# Sensor.net
KiCad netlist of a schematic drawn in Altium Designer
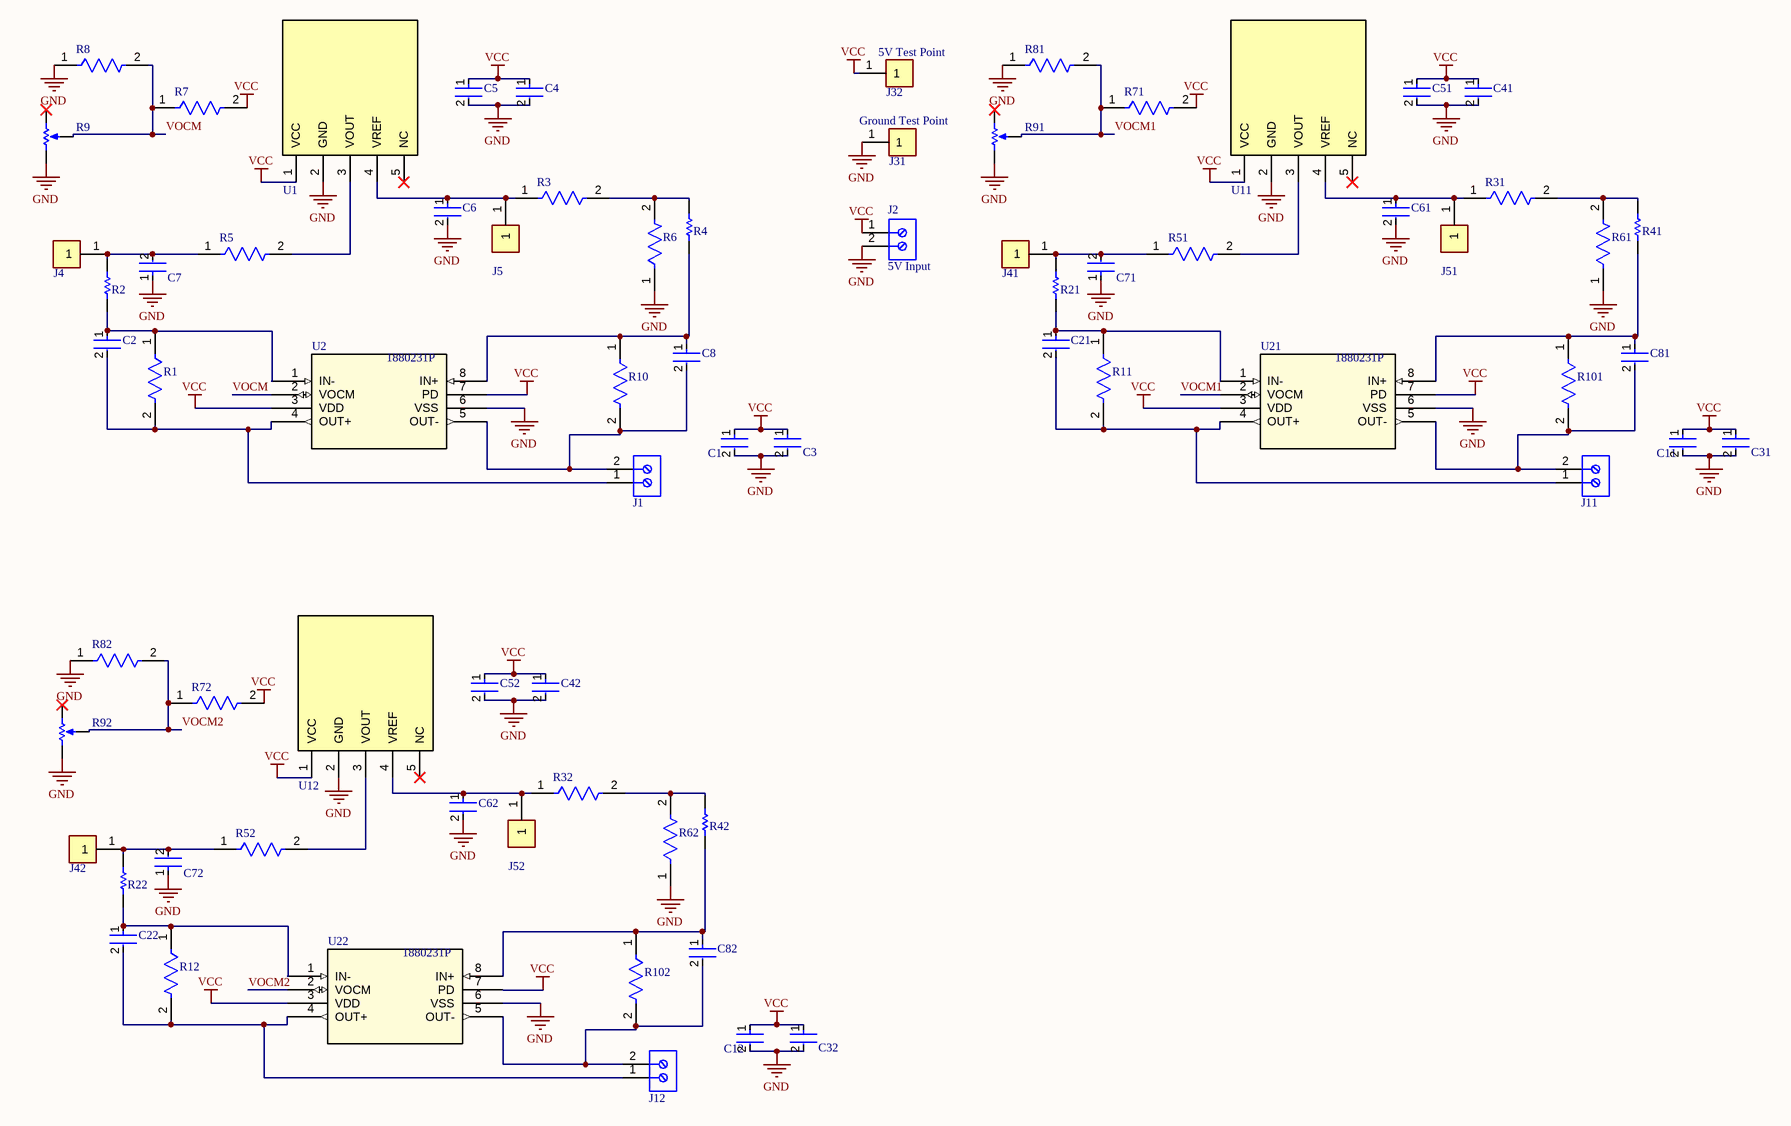
[diagram p0: Sensor.SchDoc]

(export (version "E")
  (design (tool "Eeschema 10.0.6"))
  (components
    (comp (ref "C1")
      (value "0805YC105KAT2A")
      (footprint "FP-0805-L_2_01_0_2-W_1_25-IPC_A")
      (description "General Purpose Ceramic Capacitor, 0805, 1uF, 10%, X7R, 15%, 16V")
      (fields (field (name "TOLERANCE") "10%") (field (name "VOLTAGE") "16V"))
      (libsource (lib "Altium Content Vault") (part "b4654b650e69147ec39a6b967a45e02"))
    )
    (comp (ref "C2")
      (value "06035A100JAT2A")
      (footprint "FP-0603-L_1_6_0_15-W_0_81-MFG")
      (description "General Purpose Ceramic Capacitor, 0603, 10pF, 5%, NP0, 30ppm/°C, 50V")
      (fields (field (name "TOLERANCE") "5%") (field (name "VOLTAGE") "50V"))
      (libsource (lib "Altium Content Vault") (part "02cd4be3c70576c341d710602a673aa"))
    )
    (comp (ref "C3")
      (value "CL21B104KACNNNC")
      (footprint "FP-CL21-IPC_C")
      (description "CL21 Series 0805 100nF 25V ±10% Tolerance X7R Multilayer Ceramic Chip Capacitor")
      (fields (field (name "VOLTAGE") "25V") (field (name "TOLERANCE") "10%"))
      (libsource (lib "Altium Content Vault") (part "b4654b650e69147ec39a6b967a45e02"))
    )
    (comp (ref "C4")
      (value "CL21A106KPFNNNG")
      (footprint "FP-CL21-IPC_B")
      (description "CL21 Series 0805 10uF 10V ±10% Tolerance X5R Multilayer Ceramic Chip Capacitor")
      (fields (field (name "VOLTAGE") "10V") (field (name "TOLERANCE") "10%"))
      (libsource (lib "Altium Content Vault") (part "b4654b650e69147ec39a6b967a45e02"))
    )
    (comp (ref "C5")
      (value "CL21B104KACNNNC")
      (footprint "FP-CL21-IPC_C")
      (description "CL21 Series 0805 100nF 25V ±10% Tolerance X7R Multilayer Ceramic Chip Capacitor")
      (fields (field (name "VOLTAGE") "25V") (field (name "TOLERANCE") "10%"))
      (libsource (lib "Altium Content Vault") (part "b4654b650e69147ec39a6b967a45e02"))
    )
    (comp (ref "C6")
      (value "CL21B104KACNNNC")
      (footprint "FP-CL21-IPC_C")
      (description "CL21 Series 0805 100nF 25V ±10% Tolerance X7R Multilayer Ceramic Chip Capacitor")
      (fields (field (name "VOLTAGE") "25V") (field (name "TOLERANCE") "10%"))
      (libsource (lib "Altium Content Vault") (part "b4654b650e69147ec39a6b967a45e02"))
    )
    (comp (ref "C7")
      (value "06035A100JAT2A")
      (footprint "FP-0603-L_1_6_0_15-W_0_81-MFG")
      (description "General Purpose Ceramic Capacitor, 0603, 10pF, 5%, NP0, 30ppm/°C, 50V")
      (fields (field (name "TOLERANCE") "5%") (field (name "VOLTAGE") "50V"))
      (libsource (lib "Altium Content Vault") (part "02cd4be3c70576c341d710602a673aa"))
    )
    (comp (ref "C8")
      (value "06035A100JAT2A")
      (footprint "FP-0603-L_1_6_0_15-W_0_81-MFG")
      (description "General Purpose Ceramic Capacitor, 0603, 10pF, 5%, NP0, 30ppm/°C, 50V")
      (fields (field (name "TOLERANCE") "5%") (field (name "VOLTAGE") "50V"))
      (libsource (lib "Altium Content Vault") (part "02cd4be3c70576c341d710602a673aa"))
    )
    (comp (ref "C11")
      (value "0805YC105KAT2A")
      (footprint "FP-0805-L_2_01_0_2-W_1_25-IPC_A")
      (description "General Purpose Ceramic Capacitor, 0805, 1uF, 10%, X7R, 15%, 16V")
      (fields (field (name "TOLERANCE") "10%") (field (name "VOLTAGE") "16V"))
      (libsource (lib "Altium Content Vault") (part "b4654b650e69147ec39a6b967a45e02"))
    )
    (comp (ref "C12")
      (value "0805YC105KAT2A")
      (footprint "FP-0805-L_2_01_0_2-W_1_25-IPC_A")
      (description "General Purpose Ceramic Capacitor, 0805, 1uF, 10%, X7R, 15%, 16V")
      (fields (field (name "TOLERANCE") "10%") (field (name "VOLTAGE") "16V"))
      (libsource (lib "Altium Content Vault") (part "b4654b650e69147ec39a6b967a45e02"))
    )
    (comp (ref "C21")
      (value "06035A100JAT2A")
      (footprint "FP-0603-L_1_6_0_15-W_0_81-MFG")
      (description "General Purpose Ceramic Capacitor, 0603, 10pF, 5%, NP0, 30ppm/°C, 50V")
      (fields (field (name "TOLERANCE") "5%") (field (name "VOLTAGE") "50V"))
      (libsource (lib "Altium Content Vault") (part "02cd4be3c70576c341d710602a673aa"))
    )
    (comp (ref "C22")
      (value "06035A100JAT2A")
      (footprint "FP-0603-L_1_6_0_15-W_0_81-MFG")
      (description "General Purpose Ceramic Capacitor, 0603, 10pF, 5%, NP0, 30ppm/°C, 50V")
      (fields (field (name "TOLERANCE") "5%") (field (name "VOLTAGE") "50V"))
      (libsource (lib "Altium Content Vault") (part "02cd4be3c70576c341d710602a673aa"))
    )
    (comp (ref "C31")
      (value "CL21B104KACNNNC")
      (footprint "FP-CL21-IPC_C")
      (description "CL21 Series 0805 100nF 25V ±10% Tolerance X7R Multilayer Ceramic Chip Capacitor")
      (fields (field (name "VOLTAGE") "25V") (field (name "TOLERANCE") "10%"))
      (libsource (lib "Altium Content Vault") (part "b4654b650e69147ec39a6b967a45e02"))
    )
    (comp (ref "C32")
      (value "CL21B104KACNNNC")
      (footprint "FP-CL21-IPC_C")
      (description "CL21 Series 0805 100nF 25V ±10% Tolerance X7R Multilayer Ceramic Chip Capacitor")
      (fields (field (name "VOLTAGE") "25V") (field (name "TOLERANCE") "10%"))
      (libsource (lib "Altium Content Vault") (part "b4654b650e69147ec39a6b967a45e02"))
    )
    (comp (ref "C41")
      (value "CL21A106KPFNNNG")
      (footprint "FP-CL21-IPC_B")
      (description "CL21 Series 0805 10uF 10V ±10% Tolerance X5R Multilayer Ceramic Chip Capacitor")
      (fields (field (name "VOLTAGE") "10V") (field (name "TOLERANCE") "10%"))
      (libsource (lib "Altium Content Vault") (part "b4654b650e69147ec39a6b967a45e02"))
    )
    (comp (ref "C42")
      (value "CL21A106KPFNNNG")
      (footprint "FP-CL21-IPC_B")
      (description "CL21 Series 0805 10uF 10V ±10% Tolerance X5R Multilayer Ceramic Chip Capacitor")
      (fields (field (name "VOLTAGE") "10V") (field (name "TOLERANCE") "10%"))
      (libsource (lib "Altium Content Vault") (part "b4654b650e69147ec39a6b967a45e02"))
    )
    (comp (ref "C51")
      (value "CL21B104KACNNNC")
      (footprint "FP-CL21-IPC_C")
      (description "CL21 Series 0805 100nF 25V ±10% Tolerance X7R Multilayer Ceramic Chip Capacitor")
      (fields (field (name "VOLTAGE") "25V") (field (name "TOLERANCE") "10%"))
      (libsource (lib "Altium Content Vault") (part "b4654b650e69147ec39a6b967a45e02"))
    )
    (comp (ref "C52")
      (value "CL21B104KACNNNC")
      (footprint "FP-CL21-IPC_C")
      (description "CL21 Series 0805 100nF 25V ±10% Tolerance X7R Multilayer Ceramic Chip Capacitor")
      (fields (field (name "VOLTAGE") "25V") (field (name "TOLERANCE") "10%"))
      (libsource (lib "Altium Content Vault") (part "b4654b650e69147ec39a6b967a45e02"))
    )
    (comp (ref "C61")
      (value "CL21B104KACNNNC")
      (footprint "FP-CL21-IPC_C")
      (description "CL21 Series 0805 100nF 25V ±10% Tolerance X7R Multilayer Ceramic Chip Capacitor")
      (fields (field (name "VOLTAGE") "25V") (field (name "TOLERANCE") "10%"))
      (libsource (lib "Altium Content Vault") (part "b4654b650e69147ec39a6b967a45e02"))
    )
    (comp (ref "C62")
      (value "CL21B104KACNNNC")
      (footprint "FP-CL21-IPC_C")
      (description "CL21 Series 0805 100nF 25V ±10% Tolerance X7R Multilayer Ceramic Chip Capacitor")
      (fields (field (name "VOLTAGE") "25V") (field (name "TOLERANCE") "10%"))
      (libsource (lib "Altium Content Vault") (part "b4654b650e69147ec39a6b967a45e02"))
    )
    (comp (ref "C71")
      (value "06035A100JAT2A")
      (footprint "FP-0603-L_1_6_0_15-W_0_81-MFG")
      (description "General Purpose Ceramic Capacitor, 0603, 10pF, 5%, NP0, 30ppm/°C, 50V")
      (fields (field (name "TOLERANCE") "5%") (field (name "VOLTAGE") "50V"))
      (libsource (lib "Altium Content Vault") (part "02cd4be3c70576c341d710602a673aa"))
    )
    (comp (ref "C72")
      (value "06035A100JAT2A")
      (footprint "FP-0603-L_1_6_0_15-W_0_81-MFG")
      (description "General Purpose Ceramic Capacitor, 0603, 10pF, 5%, NP0, 30ppm/°C, 50V")
      (fields (field (name "TOLERANCE") "5%") (field (name "VOLTAGE") "50V"))
      (libsource (lib "Altium Content Vault") (part "02cd4be3c70576c341d710602a673aa"))
    )
    (comp (ref "C81")
      (value "06035A100JAT2A")
      (footprint "FP-0603-L_1_6_0_15-W_0_81-MFG")
      (description "General Purpose Ceramic Capacitor, 0603, 10pF, 5%, NP0, 30ppm/°C, 50V")
      (fields (field (name "TOLERANCE") "5%") (field (name "VOLTAGE") "50V"))
      (libsource (lib "Altium Content Vault") (part "02cd4be3c70576c341d710602a673aa"))
    )
    (comp (ref "C82")
      (value "06035A100JAT2A")
      (footprint "FP-0603-L_1_6_0_15-W_0_81-MFG")
      (description "General Purpose Ceramic Capacitor, 0603, 10pF, 5%, NP0, 30ppm/°C, 50V")
      (fields (field (name "TOLERANCE") "5%") (field (name "VOLTAGE") "50V"))
      (libsource (lib "Altium Content Vault") (part "02cd4be3c70576c341d710602a673aa"))
    )
    (comp (ref "J1")
      (value "691213510002")
      (footprint "691213510002")
      (description "Serie 2135 - 5.08 mm Horizontal Entry Modular with Rising Cage Clamp WR-TBL, 2 pin")
      (fields (field (name "MANUFACTURER") "Wurth Elektronik") (field (name "PUBLISHER") "WurthElektronik"))
      (libsource (lib "Altium Content Vault") (part "WE-CN-1P-F-TB2"))
    )
    (comp (ref "J2")
      (value "5V Input")
      (footprint "691213510002")
      (description "Serie 2135 - 5.08 mm Horizontal Entry Modular with Rising Cage Clamp WR-TBL, 2 pin")
      (fields
        (field (name "PART NUMBER") "691213510002")
        (field (name "MANUFACTURER") "Wurth Elektronik")
        (field (name "PUBLISHER") "WurthElektronik")
      )
      (libsource (lib "") (part "WE-CN-1P-F-TB2_2"))
    )
    (comp (ref "J4")
      (value "5001")
      (footprint "FP-5001-MFG")
      (description "PC TEST POINT MINIATURE BLACK")
      (libsource (lib "") (part "1e4615820a309e3ce90f9e6d957b7fa_1"))
    )
    (comp (ref "J5")
      (value "5001")
      (footprint "FP-5001-MFG")
      (description "PC TEST POINT MINIATURE BLACK")
      (libsource (lib "") (part "1e4615820a309e3ce90f9e6d957b7fa_2"))
    )
    (comp (ref "J11")
      (value "691213510002")
      (footprint "691213510002")
      (description "Serie 2135 - 5.08 mm Horizontal Entry Modular with Rising Cage Clamp WR-TBL, 2 pin")
      (fields (field (name "MANUFACTURER") "Wurth Elektronik") (field (name "PUBLISHER") "WurthElektronik"))
      (libsource (lib "") (part "WE-CN-1P-F-TB2_1"))
    )
    (comp (ref "J12")
      (value "691213510002")
      (footprint "691213510002")
      (description "Serie 2135 - 5.08 mm Horizontal Entry Modular with Rising Cage Clamp WR-TBL, 2 pin")
      (fields (field (name "MANUFACTURER") "Wurth Elektronik") (field (name "PUBLISHER") "WurthElektronik"))
      (libsource (lib "Altium Content Vault") (part "WE-CN-1P-F-TB2"))
    )
    (comp (ref "J31")
      (value "Ground Test Point")
      (footprint "FP-5001-MFG")
      (description "PC TEST POINT MINIATURE BLACK")
      (libsource (lib "Altium Content Vault") (part "1e4615820a309e3ce90f9e6d957b7fa"))
    )
    (comp (ref "J32")
      (value "5V Test Point")
      (footprint "FP-5001-MFG")
      (description "PC TEST POINT MINIATURE BLACK")
      (libsource (lib "Altium Content Vault") (part "1e4615820a309e3ce90f9e6d957b7fa"))
    )
    (comp (ref "J41")
      (value "5001")
      (footprint "FP-5001-MFG")
      (description "PC TEST POINT MINIATURE BLACK")
      (libsource (lib "") (part "1e4615820a309e3ce90f9e6d957b7fa_1"))
    )
    (comp (ref "J42")
      (value "5001")
      (footprint "FP-5001-MFG")
      (description "PC TEST POINT MINIATURE BLACK")
      (libsource (lib "") (part "1e4615820a309e3ce90f9e6d957b7fa_1"))
    )
    (comp (ref "J51")
      (value "5001")
      (footprint "FP-5001-MFG")
      (description "PC TEST POINT MINIATURE BLACK")
      (libsource (lib "") (part "1e4615820a309e3ce90f9e6d957b7fa_2"))
    )
    (comp (ref "J52")
      (value "5001")
      (footprint "FP-5001-MFG")
      (description "PC TEST POINT MINIATURE BLACK")
      (libsource (lib "") (part "1e4615820a309e3ce90f9e6d957b7fa_2"))
    )
    (comp (ref "R1")
      (value "RNCP0805FTD1K00")
      (footprint "FP-RNCP0805-MFG")
      (description "1kΩ ±1% 0.25W 0805 High Power Anti-Sulfur Thin Film Chip Resistor")
      (fields (field (name "TOLERANCE") "1%"))
      (libsource (lib "Altium Content Vault") (part "1029c3af85768c4190bb7ad29bc67b5"))
    )
    (comp (ref "R2")
      (value "RK73H2ATTD1331F")
      (footprint "RESC2013X60X30NL20T20")
      (fields (field (name "MANUFACTURER") "KOA Speer"))
      (libsource (lib "Altium Content Vault") (part "RES"))
    )
    (comp (ref "R3")
      (value "RMCF0805ZT0R00")
      (footprint "FP-RMCF0805-MFG")
      (description "RES 0 OHM JUMPER 1/8W 0805")
      (libsource (lib "Altium Content Vault") (part "1029c3af85768c4190bb7ad29bc67b5"))
    )
    (comp (ref "R4")
      (value "RK73H2ATTD1331F")
      (footprint "RESC2013X60X30NL20T20")
      (fields (field (name "MANUFACTURER") "KOA Speer"))
      (libsource (lib "Altium Content Vault") (part "RES"))
    )
    (comp (ref "R5")
      (value "RMCF0805ZT0R00")
      (footprint "FP-RMCF0805-MFG")
      (description "RES 0 OHM JUMPER 1/8W 0805")
      (libsource (lib "Altium Content Vault") (part "1029c3af85768c4190bb7ad29bc67b5"))
    )
    (comp (ref "R6")
      (value "RMCF0805ZT0R00")
      (footprint "FP-RMCF0805-MFG")
      (description "RES 0 OHM JUMPER 1/8W 0805")
      (libsource (lib "Altium Content Vault") (part "1029c3af85768c4190bb7ad29bc67b5"))
    )
    (comp (ref "R7")
      (value "RT0805DRE0710KL")
      (footprint "FP-RT0805-MFG")
      (description "RES 10.0K OHM 1/8W .5% SMD 0805")
      (fields (field (name "MANUFACTURER") "Yageo") (field (name "TOLERANCE") "0.01"))
      (libsource (lib "Altium Content Vault") (part "1029c3af85768c4190bb7ad29bc67b5"))
    )
    (comp (ref "R8")
      (value "RMCF0805ZT0R00")
      (footprint "FP-RMCF0805-MFG")
      (description "RES 0 OHM JUMPER 1/8W 0805")
      (libsource (lib "Altium Content Vault") (part "1029c3af85768c4190bb7ad29bc67b5"))
    )
    (comp (ref "R9")
      (value "3296W-1-103LF")
      (footprint "BOUR-3296W")
      (fields (field (name "TOLERANCE") "1%"))
      (libsource (lib "Altium Content Vault") (part "RES-POT-3"))
    )
    (comp (ref "R10")
      (value "RNCP0805FTD1K00")
      (footprint "FP-RNCP0805-MFG")
      (description "1kΩ ±1% 0.25W 0805 High Power Anti-Sulfur Thin Film Chip Resistor")
      (fields (field (name "TOLERANCE") "1%"))
      (libsource (lib "Altium Content Vault") (part "1029c3af85768c4190bb7ad29bc67b5"))
    )
    (comp (ref "R11")
      (value "RNCP0805FTD1K00")
      (footprint "FP-RNCP0805-MFG")
      (description "1kΩ ±1% 0.25W 0805 High Power Anti-Sulfur Thin Film Chip Resistor")
      (fields (field (name "TOLERANCE") "1%"))
      (libsource (lib "Altium Content Vault") (part "1029c3af85768c4190bb7ad29bc67b5"))
    )
    (comp (ref "R12")
      (value "RNCP0805FTD1K00")
      (footprint "FP-RNCP0805-MFG")
      (description "1kΩ ±1% 0.25W 0805 High Power Anti-Sulfur Thin Film Chip Resistor")
      (fields (field (name "TOLERANCE") "1%"))
      (libsource (lib "Altium Content Vault") (part "1029c3af85768c4190bb7ad29bc67b5"))
    )
    (comp (ref "R21")
      (value "RK73H2ATTD1331F")
      (footprint "RESC2013X60X30NL20T20")
      (fields (field (name "MANUFACTURER") "KOA Speer"))
      (libsource (lib "Altium Content Vault") (part "RES"))
    )
    (comp (ref "R22")
      (value "RK73H2ATTD1331F")
      (footprint "RESC2013X60X30NL20T20")
      (fields (field (name "MANUFACTURER") "KOA Speer"))
      (libsource (lib "Altium Content Vault") (part "RES"))
    )
    (comp (ref "R31")
      (value "RMCF0805ZT0R00")
      (footprint "FP-RMCF0805-MFG")
      (description "RES 0 OHM JUMPER 1/8W 0805")
      (libsource (lib "Altium Content Vault") (part "1029c3af85768c4190bb7ad29bc67b5"))
    )
    (comp (ref "R32")
      (value "RMCF0805ZT0R00")
      (footprint "FP-RMCF0805-MFG")
      (description "RES 0 OHM JUMPER 1/8W 0805")
      (libsource (lib "Altium Content Vault") (part "1029c3af85768c4190bb7ad29bc67b5"))
    )
    (comp (ref "R41")
      (value "RK73H2ATTD1331F")
      (footprint "RESC2013X60X30NL20T20")
      (fields (field (name "MANUFACTURER") "KOA Speer"))
      (libsource (lib "Altium Content Vault") (part "RES"))
    )
    (comp (ref "R42")
      (value "RK73H2ATTD1331F")
      (footprint "RESC2013X60X30NL20T20")
      (fields (field (name "MANUFACTURER") "KOA Speer"))
      (libsource (lib "Altium Content Vault") (part "RES"))
    )
    (comp (ref "R51")
      (value "RMCF0805ZT0R00")
      (footprint "FP-RMCF0805-MFG")
      (description "RES 0 OHM JUMPER 1/8W 0805")
      (libsource (lib "Altium Content Vault") (part "1029c3af85768c4190bb7ad29bc67b5"))
    )
    (comp (ref "R52")
      (value "RMCF0805ZT0R00")
      (footprint "FP-RMCF0805-MFG")
      (description "RES 0 OHM JUMPER 1/8W 0805")
      (libsource (lib "Altium Content Vault") (part "1029c3af85768c4190bb7ad29bc67b5"))
    )
    (comp (ref "R61")
      (value "RMCF0805ZT0R00")
      (footprint "FP-RMCF0805-MFG")
      (description "RES 0 OHM JUMPER 1/8W 0805")
      (libsource (lib "Altium Content Vault") (part "1029c3af85768c4190bb7ad29bc67b5"))
    )
    (comp (ref "R62")
      (value "RMCF0805ZT0R00")
      (footprint "FP-RMCF0805-MFG")
      (description "RES 0 OHM JUMPER 1/8W 0805")
      (libsource (lib "Altium Content Vault") (part "1029c3af85768c4190bb7ad29bc67b5"))
    )
    (comp (ref "R71")
      (value "RT0805DRE0710KL")
      (footprint "FP-RT0805-MFG")
      (description "RES 10.0K OHM 1/8W .5% SMD 0805")
      (fields (field (name "MANUFACTURER") "Yageo") (field (name "TOLERANCE") "0.01"))
      (libsource (lib "Altium Content Vault") (part "1029c3af85768c4190bb7ad29bc67b5"))
    )
    (comp (ref "R72")
      (value "RT0805DRE0710KL")
      (footprint "FP-RT0805-MFG")
      (description "RES 10.0K OHM 1/8W .5% SMD 0805")
      (fields (field (name "MANUFACTURER") "Yageo") (field (name "TOLERANCE") "0.01"))
      (libsource (lib "Altium Content Vault") (part "1029c3af85768c4190bb7ad29bc67b5"))
    )
    (comp (ref "R81")
      (value "RMCF0805ZT0R00")
      (footprint "FP-RMCF0805-MFG")
      (description "RES 0 OHM JUMPER 1/8W 0805")
      (libsource (lib "Altium Content Vault") (part "1029c3af85768c4190bb7ad29bc67b5"))
    )
    (comp (ref "R82")
      (value "RMCF0805ZT0R00")
      (footprint "FP-RMCF0805-MFG")
      (description "RES 0 OHM JUMPER 1/8W 0805")
      (libsource (lib "Altium Content Vault") (part "1029c3af85768c4190bb7ad29bc67b5"))
    )
    (comp (ref "R91")
      (value "3296W-1-103LF")
      (footprint "BOUR-3296W")
      (fields (field (name "TOLERANCE") "1%"))
      (libsource (lib "Altium Content Vault") (part "RES-POT-3"))
    )
    (comp (ref "R92")
      (value "3296W-1-103LF")
      (footprint "BOUR-3296W")
      (fields (field (name "TOLERANCE") "1%"))
      (libsource (lib "Altium Content Vault") (part "RES-POT-3"))
    )
    (comp (ref "R101")
      (value "RNCP0805FTD1K00")
      (footprint "FP-RNCP0805-MFG")
      (description "1kΩ ±1% 0.25W 0805 High Power Anti-Sulfur Thin Film Chip Resistor")
      (fields (field (name "TOLERANCE") "1%"))
      (libsource (lib "Altium Content Vault") (part "1029c3af85768c4190bb7ad29bc67b5"))
    )
    (comp (ref "R102")
      (value "RNCP0805FTD1K00")
      (footprint "FP-RNCP0805-MFG")
      (description "1kΩ ±1% 0.25W 0805 High Power Anti-Sulfur Thin Film Chip Resistor")
      (fields (field (name "TOLERANCE") "1%"))
      (libsource (lib "Altium Content Vault") (part "1029c3af85768c4190bb7ad29bc67b5"))
    )
    (comp (ref "U1")
      (value "STB-LA/Z")
      (footprint "STB_pad_SMT")
      (libsource (lib "STB-LAZ") (part "STB-LA/Z"))
    )
    (comp (ref "U2")
      (value "MCP6D11-E/MS")
      (footprint "MSOP8_MS_MCH")
      (description "No Description Available")
      (fields
        (field (name "SUPPLIER PART NUMBER 1") "1880231P")
        (field (name "COPYRIGHT") "Copyright (C) 2022 Ultra Librarian. All rights reserved.")
      )
      (libsource (lib "MCP6D11-E&slash_MS") (part "MCP6D11-E/MS"))
    )
    (comp (ref "U11")
      (value "STB-LA/Z")
      (footprint "STB_pad_SMT")
      (libsource (lib "STB-LAZ") (part "STB-LA/Z"))
    )
    (comp (ref "U12")
      (value "STB-LA/Z")
      (footprint "STB_pad_SMT")
      (libsource (lib "STB-LAZ") (part "STB-LA/Z"))
    )
    (comp (ref "U21")
      (value "MCP6D11-E/MS")
      (footprint "MSOP8_MS_MCH")
      (description "No Description Available")
      (fields
        (field (name "SUPPLIER PART NUMBER 1") "1880231P")
        (field (name "COPYRIGHT") "Copyright (C) 2022 Ultra Librarian. All rights reserved.")
      )
      (libsource (lib "MCP6D11-E&slash_MS") (part "MCP6D11-E/MS"))
    )
    (comp (ref "U22")
      (value "MCP6D11-E/MS")
      (footprint "MSOP8_MS_MCH")
      (description "No Description Available")
      (fields
        (field (name "SUPPLIER PART NUMBER 1") "1880231P")
        (field (name "COPYRIGHT") "Copyright (C) 2022 Ultra Librarian. All rights reserved.")
      )
      (libsource (lib "MCP6D11-E&slash_MS") (part "MCP6D11-E/MS"))
    )
  )
  (nets
    (net (code "1") (name "/VOCM") (class "Default")
      (node (ref "R7") (pin "1") (pinfunction "1_1") (pintype "passive"))
      (node (ref "R8") (pin "2") (pinfunction "2_2") (pintype "passive"))
      (node (ref "R9") (pin "2") (pinfunction "S_2") (pintype "passive"))
      (node (ref "U2") (pin "2") (pinfunction "VOCM_2") (pintype "bidirectional"))
    )
    (net (code "2") (name "/VOCM1") (class "Default")
      (node (ref "R71") (pin "1") (pinfunction "1_1") (pintype "passive"))
      (node (ref "R81") (pin "2") (pinfunction "2_2") (pintype "passive"))
      (node (ref "R91") (pin "2") (pinfunction "S_2") (pintype "passive"))
      (node (ref "U21") (pin "2") (pinfunction "VOCM_2") (pintype "bidirectional"))
    )
    (net (code "3") (name "/VOCM2") (class "Default")
      (node (ref "R72") (pin "1") (pinfunction "1_1") (pintype "passive"))
      (node (ref "R82") (pin "2") (pinfunction "2_2") (pintype "passive"))
      (node (ref "R92") (pin "2") (pinfunction "S_2") (pintype "passive"))
      (node (ref "U22") (pin "2") (pinfunction "VOCM_2") (pintype "bidirectional"))
    )
    (net (code "4") (name "GND") (class "Default")
      (node (ref "C1") (pin "2") (pinfunction "2_2") (pintype "passive"))
      (node (ref "C11") (pin "2") (pinfunction "2_2") (pintype "passive"))
      (node (ref "C12") (pin "2") (pinfunction "2_2") (pintype "passive"))
      (node (ref "C3") (pin "2") (pinfunction "2_2") (pintype "passive"))
      (node (ref "C31") (pin "2") (pinfunction "2_2") (pintype "passive"))
      (node (ref "C32") (pin "2") (pinfunction "2_2") (pintype "passive"))
      (node (ref "C4") (pin "2") (pinfunction "2_2") (pintype "passive"))
      (node (ref "C41") (pin "2") (pinfunction "2_2") (pintype "passive"))
      (node (ref "C42") (pin "2") (pinfunction "2_2") (pintype "passive"))
      (node (ref "C5") (pin "2") (pinfunction "2_2") (pintype "passive"))
      (node (ref "C51") (pin "2") (pinfunction "2_2") (pintype "passive"))
      (node (ref "C52") (pin "2") (pinfunction "2_2") (pintype "passive"))
      (node (ref "C6") (pin "2") (pinfunction "2_2") (pintype "passive"))
      (node (ref "C61") (pin "2") (pinfunction "2_2") (pintype "passive"))
      (node (ref "C62") (pin "2") (pinfunction "2_2") (pintype "passive"))
      (node (ref "C7") (pin "1") (pinfunction "1_1") (pintype "passive"))
      (node (ref "C71") (pin "1") (pinfunction "1_1") (pintype "passive"))
      (node (ref "C72") (pin "1") (pinfunction "1_1") (pintype "passive"))
      (node (ref "J2") (pin "2") (pinfunction "2_2") (pintype "passive"))
      (node (ref "J31") (pin "1") (pinfunction "1_1") (pintype "passive"))
      (node (ref "R6") (pin "1") (pinfunction "1_1") (pintype "passive"))
      (node (ref "R61") (pin "1") (pinfunction "1_1") (pintype "passive"))
      (node (ref "R62") (pin "1") (pinfunction "1_1") (pintype "passive"))
      (node (ref "R8") (pin "1") (pinfunction "1_1") (pintype "passive"))
      (node (ref "R81") (pin "1") (pinfunction "1_1") (pintype "passive"))
      (node (ref "R82") (pin "1") (pinfunction "1_1") (pintype "passive"))
      (node (ref "R9") (pin "1") (pinfunction "CCW_1") (pintype "passive"))
      (node (ref "R91") (pin "1") (pinfunction "CCW_1") (pintype "passive"))
      (node (ref "R92") (pin "1") (pinfunction "CCW_1") (pintype "passive"))
      (node (ref "U1") (pin "2") (pinfunction "GND_2") (pintype "passive"))
      (node (ref "U11") (pin "2") (pinfunction "GND_2") (pintype "passive"))
      (node (ref "U12") (pin "2") (pinfunction "GND_2") (pintype "passive"))
      (node (ref "U2") (pin "6") (pinfunction "VSS_6") (pintype "passive"))
      (node (ref "U21") (pin "6") (pinfunction "VSS_6") (pintype "passive"))
      (node (ref "U22") (pin "6") (pinfunction "VSS_6") (pintype "passive"))
    )
    (net (code "5") (name "Net-(C7-Pad2)") (class "Default")
      (node (ref "C7") (pin "2") (pinfunction "2_2") (pintype "passive"))
      (node (ref "J4") (pin "1") (pinfunction "1_1") (pintype "passive"))
      (node (ref "R2") (pin "2") (pinfunction "2_2") (pintype "passive"))
      (node (ref "R5") (pin "1") (pinfunction "1_1") (pintype "passive"))
    )
    (net (code "6") (name "Net-(C71-Pad2)") (class "Default")
      (node (ref "C71") (pin "2") (pinfunction "2_2") (pintype "passive"))
      (node (ref "J41") (pin "1") (pinfunction "1_1") (pintype "passive"))
      (node (ref "R21") (pin "2") (pinfunction "2_2") (pintype "passive"))
      (node (ref "R51") (pin "1") (pinfunction "1_1") (pintype "passive"))
    )
    (net (code "7") (name "Net-(C72-Pad2)") (class "Default")
      (node (ref "C72") (pin "2") (pinfunction "2_2") (pintype "passive"))
      (node (ref "J42") (pin "1") (pinfunction "1_1") (pintype "passive"))
      (node (ref "R22") (pin "2") (pinfunction "2_2") (pintype "passive"))
      (node (ref "R52") (pin "1") (pinfunction "1_1") (pintype "passive"))
    )
    (net (code "8") (name "Net-(R3-Pad2)") (class "Default")
      (node (ref "R3") (pin "2") (pinfunction "2_2") (pintype "passive"))
      (node (ref "R4") (pin "2") (pinfunction "2_2") (pintype "passive"))
      (node (ref "R6") (pin "2") (pinfunction "2_2") (pintype "passive"))
    )
    (net (code "9") (name "Net-(R31-Pad2)") (class "Default")
      (node (ref "R31") (pin "2") (pinfunction "2_2") (pintype "passive"))
      (node (ref "R41") (pin "2") (pinfunction "2_2") (pintype "passive"))
      (node (ref "R61") (pin "2") (pinfunction "2_2") (pintype "passive"))
    )
    (net (code "10") (name "Net-(R32-Pad2)") (class "Default")
      (node (ref "R32") (pin "2") (pinfunction "2_2") (pintype "passive"))
      (node (ref "R42") (pin "2") (pinfunction "2_2") (pintype "passive"))
      (node (ref "R62") (pin "2") (pinfunction "2_2") (pintype "passive"))
    )
    (net (code "11") (name "Net-(U1-VOUT)") (class "Default")
      (node (ref "R5") (pin "2") (pinfunction "2_2") (pintype "passive"))
      (node (ref "U1") (pin "3") (pinfunction "VOUT_3") (pintype "passive"))
    )
    (net (code "12") (name "Net-(U1-VREF)") (class "Default")
      (node (ref "C6") (pin "1") (pinfunction "1_1") (pintype "passive"))
      (node (ref "J5") (pin "1") (pinfunction "1_1") (pintype "passive"))
      (node (ref "R3") (pin "1") (pinfunction "1_1") (pintype "passive"))
      (node (ref "U1") (pin "4") (pinfunction "VREF_4") (pintype "passive"))
    )
    (net (code "13") (name "Net-(U2-IN+)") (class "Default")
      (node (ref "C8") (pin "1") (pinfunction "1_1") (pintype "passive"))
      (node (ref "R10") (pin "1") (pinfunction "1_1") (pintype "passive"))
      (node (ref "R4") (pin "1") (pinfunction "1_1") (pintype "passive"))
      (node (ref "U2") (pin "8") (pinfunction "IN+_8") (pintype "input"))
    )
    (net (code "14") (name "Net-(U2-IN-)") (class "Default")
      (node (ref "C2") (pin "1") (pinfunction "1_1") (pintype "passive"))
      (node (ref "R1") (pin "1") (pinfunction "1_1") (pintype "passive"))
      (node (ref "R2") (pin "1") (pinfunction "1_1") (pintype "passive"))
      (node (ref "U2") (pin "1") (pinfunction "IN-_1") (pintype "input"))
    )
    (net (code "15") (name "Net-(U2-OUT+)") (class "Default")
      (node (ref "C2") (pin "2") (pinfunction "2_2") (pintype "passive"))
      (node (ref "J1") (pin "1") (pinfunction "1_1") (pintype "passive"))
      (node (ref "R1") (pin "2") (pinfunction "2_2") (pintype "passive"))
      (node (ref "U2") (pin "4") (pinfunction "OUT+_4") (pintype "output"))
    )
    (net (code "16") (name "Net-(U2-OUT-)") (class "Default")
      (node (ref "C8") (pin "2") (pinfunction "2_2") (pintype "passive"))
      (node (ref "J1") (pin "2") (pinfunction "2_2") (pintype "passive"))
      (node (ref "R10") (pin "2") (pinfunction "2_2") (pintype "passive"))
      (node (ref "U2") (pin "5") (pinfunction "OUT-_5") (pintype "output"))
    )
    (net (code "17") (name "Net-(U11-VOUT)") (class "Default")
      (node (ref "R51") (pin "2") (pinfunction "2_2") (pintype "passive"))
      (node (ref "U11") (pin "3") (pinfunction "VOUT_3") (pintype "passive"))
    )
    (net (code "18") (name "Net-(U11-VREF)") (class "Default")
      (node (ref "C61") (pin "1") (pinfunction "1_1") (pintype "passive"))
      (node (ref "J51") (pin "1") (pinfunction "1_1") (pintype "passive"))
      (node (ref "R31") (pin "1") (pinfunction "1_1") (pintype "passive"))
      (node (ref "U11") (pin "4") (pinfunction "VREF_4") (pintype "passive"))
    )
    (net (code "19") (name "Net-(U12-VOUT)") (class "Default")
      (node (ref "R52") (pin "2") (pinfunction "2_2") (pintype "passive"))
      (node (ref "U12") (pin "3") (pinfunction "VOUT_3") (pintype "passive"))
    )
    (net (code "20") (name "Net-(U12-VREF)") (class "Default")
      (node (ref "C62") (pin "1") (pinfunction "1_1") (pintype "passive"))
      (node (ref "J52") (pin "1") (pinfunction "1_1") (pintype "passive"))
      (node (ref "R32") (pin "1") (pinfunction "1_1") (pintype "passive"))
      (node (ref "U12") (pin "4") (pinfunction "VREF_4") (pintype "passive"))
    )
    (net (code "21") (name "Net-(U21-IN+)") (class "Default")
      (node (ref "C81") (pin "1") (pinfunction "1_1") (pintype "passive"))
      (node (ref "R101") (pin "1") (pinfunction "1_1") (pintype "passive"))
      (node (ref "R41") (pin "1") (pinfunction "1_1") (pintype "passive"))
      (node (ref "U21") (pin "8") (pinfunction "IN+_8") (pintype "input"))
    )
    (net (code "22") (name "Net-(U21-IN-)") (class "Default")
      (node (ref "C21") (pin "1") (pinfunction "1_1") (pintype "passive"))
      (node (ref "R11") (pin "1") (pinfunction "1_1") (pintype "passive"))
      (node (ref "R21") (pin "1") (pinfunction "1_1") (pintype "passive"))
      (node (ref "U21") (pin "1") (pinfunction "IN-_1") (pintype "input"))
    )
    (net (code "23") (name "Net-(U21-OUT+)") (class "Default")
      (node (ref "C21") (pin "2") (pinfunction "2_2") (pintype "passive"))
      (node (ref "J11") (pin "1") (pinfunction "1_1") (pintype "passive"))
      (node (ref "R11") (pin "2") (pinfunction "2_2") (pintype "passive"))
      (node (ref "U21") (pin "4") (pinfunction "OUT+_4") (pintype "output"))
    )
    (net (code "24") (name "Net-(U21-OUT-)") (class "Default")
      (node (ref "C81") (pin "2") (pinfunction "2_2") (pintype "passive"))
      (node (ref "J11") (pin "2") (pinfunction "2_2") (pintype "passive"))
      (node (ref "R101") (pin "2") (pinfunction "2_2") (pintype "passive"))
      (node (ref "U21") (pin "5") (pinfunction "OUT-_5") (pintype "output"))
    )
    (net (code "25") (name "Net-(U22-IN+)") (class "Default")
      (node (ref "C82") (pin "1") (pinfunction "1_1") (pintype "passive"))
      (node (ref "R102") (pin "1") (pinfunction "1_1") (pintype "passive"))
      (node (ref "R42") (pin "1") (pinfunction "1_1") (pintype "passive"))
      (node (ref "U22") (pin "8") (pinfunction "IN+_8") (pintype "input"))
    )
    (net (code "26") (name "Net-(U22-IN-)") (class "Default")
      (node (ref "C22") (pin "1") (pinfunction "1_1") (pintype "passive"))
      (node (ref "R12") (pin "1") (pinfunction "1_1") (pintype "passive"))
      (node (ref "R22") (pin "1") (pinfunction "1_1") (pintype "passive"))
      (node (ref "U22") (pin "1") (pinfunction "IN-_1") (pintype "input"))
    )
    (net (code "27") (name "Net-(U22-OUT+)") (class "Default")
      (node (ref "C22") (pin "2") (pinfunction "2_2") (pintype "passive"))
      (node (ref "J12") (pin "1") (pinfunction "1_1") (pintype "passive"))
      (node (ref "R12") (pin "2") (pinfunction "2_2") (pintype "passive"))
      (node (ref "U22") (pin "4") (pinfunction "OUT+_4") (pintype "output"))
    )
    (net (code "28") (name "Net-(U22-OUT-)") (class "Default")
      (node (ref "C82") (pin "2") (pinfunction "2_2") (pintype "passive"))
      (node (ref "J12") (pin "2") (pinfunction "2_2") (pintype "passive"))
      (node (ref "R102") (pin "2") (pinfunction "2_2") (pintype "passive"))
      (node (ref "U22") (pin "5") (pinfunction "OUT-_5") (pintype "output"))
    )
    (net (code "29") (name "VCC") (class "Default")
      (node (ref "C1") (pin "1") (pinfunction "1_1") (pintype "passive"))
      (node (ref "C11") (pin "1") (pinfunction "1_1") (pintype "passive"))
      (node (ref "C12") (pin "1") (pinfunction "1_1") (pintype "passive"))
      (node (ref "C3") (pin "1") (pinfunction "1_1") (pintype "passive"))
      (node (ref "C31") (pin "1") (pinfunction "1_1") (pintype "passive"))
      (node (ref "C32") (pin "1") (pinfunction "1_1") (pintype "passive"))
      (node (ref "C4") (pin "1") (pinfunction "1_1") (pintype "passive"))
      (node (ref "C41") (pin "1") (pinfunction "1_1") (pintype "passive"))
      (node (ref "C42") (pin "1") (pinfunction "1_1") (pintype "passive"))
      (node (ref "C5") (pin "1") (pinfunction "1_1") (pintype "passive"))
      (node (ref "C51") (pin "1") (pinfunction "1_1") (pintype "passive"))
      (node (ref "C52") (pin "1") (pinfunction "1_1") (pintype "passive"))
      (node (ref "J2") (pin "1") (pinfunction "1_1") (pintype "passive"))
      (node (ref "J32") (pin "1") (pinfunction "1_1") (pintype "passive"))
      (node (ref "R7") (pin "2") (pinfunction "2_2") (pintype "passive"))
      (node (ref "R71") (pin "2") (pinfunction "2_2") (pintype "passive"))
      (node (ref "R72") (pin "2") (pinfunction "2_2") (pintype "passive"))
      (node (ref "U1") (pin "1") (pinfunction "VCC_1") (pintype "passive"))
      (node (ref "U11") (pin "1") (pinfunction "VCC_1") (pintype "passive"))
      (node (ref "U12") (pin "1") (pinfunction "VCC_1") (pintype "passive"))
      (node (ref "U2") (pin "3") (pinfunction "VDD_3") (pintype "power_in"))
      (node (ref "U2") (pin "7") (pinfunction "PD_7") (pintype "power_in"))
      (node (ref "U21") (pin "3") (pinfunction "VDD_3") (pintype "power_in"))
      (node (ref "U21") (pin "7") (pinfunction "PD_7") (pintype "power_in"))
      (node (ref "U22") (pin "3") (pinfunction "VDD_3") (pintype "power_in"))
      (node (ref "U22") (pin "7") (pinfunction "PD_7") (pintype "power_in"))
    )
    (net (code "30") (name "unconnected-(R9-CW-Pad3)") (class "Default")
      (node (ref "R9") (pin "3") (pinfunction "CW_3") (pintype "passive+no_connect"))
    )
    (net (code "31") (name "unconnected-(R91-CW-Pad3)") (class "Default")
      (node (ref "R91") (pin "3") (pinfunction "CW_3") (pintype "passive+no_connect"))
    )
    (net (code "32") (name "unconnected-(R92-CW-Pad3)") (class "Default")
      (node (ref "R92") (pin "3") (pinfunction "CW_3") (pintype "passive+no_connect"))
    )
    (net (code "33") (name "unconnected-(U1-NC-Pad5)") (class "Default")
      (node (ref "U1") (pin "5") (pinfunction "NC_5") (pintype "passive+no_connect"))
    )
    (net (code "34") (name "unconnected-(U11-NC-Pad5)") (class "Default")
      (node (ref "U11") (pin "5") (pinfunction "NC_5") (pintype "passive+no_connect"))
    )
    (net (code "35") (name "unconnected-(U12-NC-Pad5)") (class "Default")
      (node (ref "U12") (pin "5") (pinfunction "NC_5") (pintype "passive+no_connect"))
    )
  )
)
